# ESP32_IMUtracker_revA.net
KiCad netlist of a schematic drawn in EAGLE
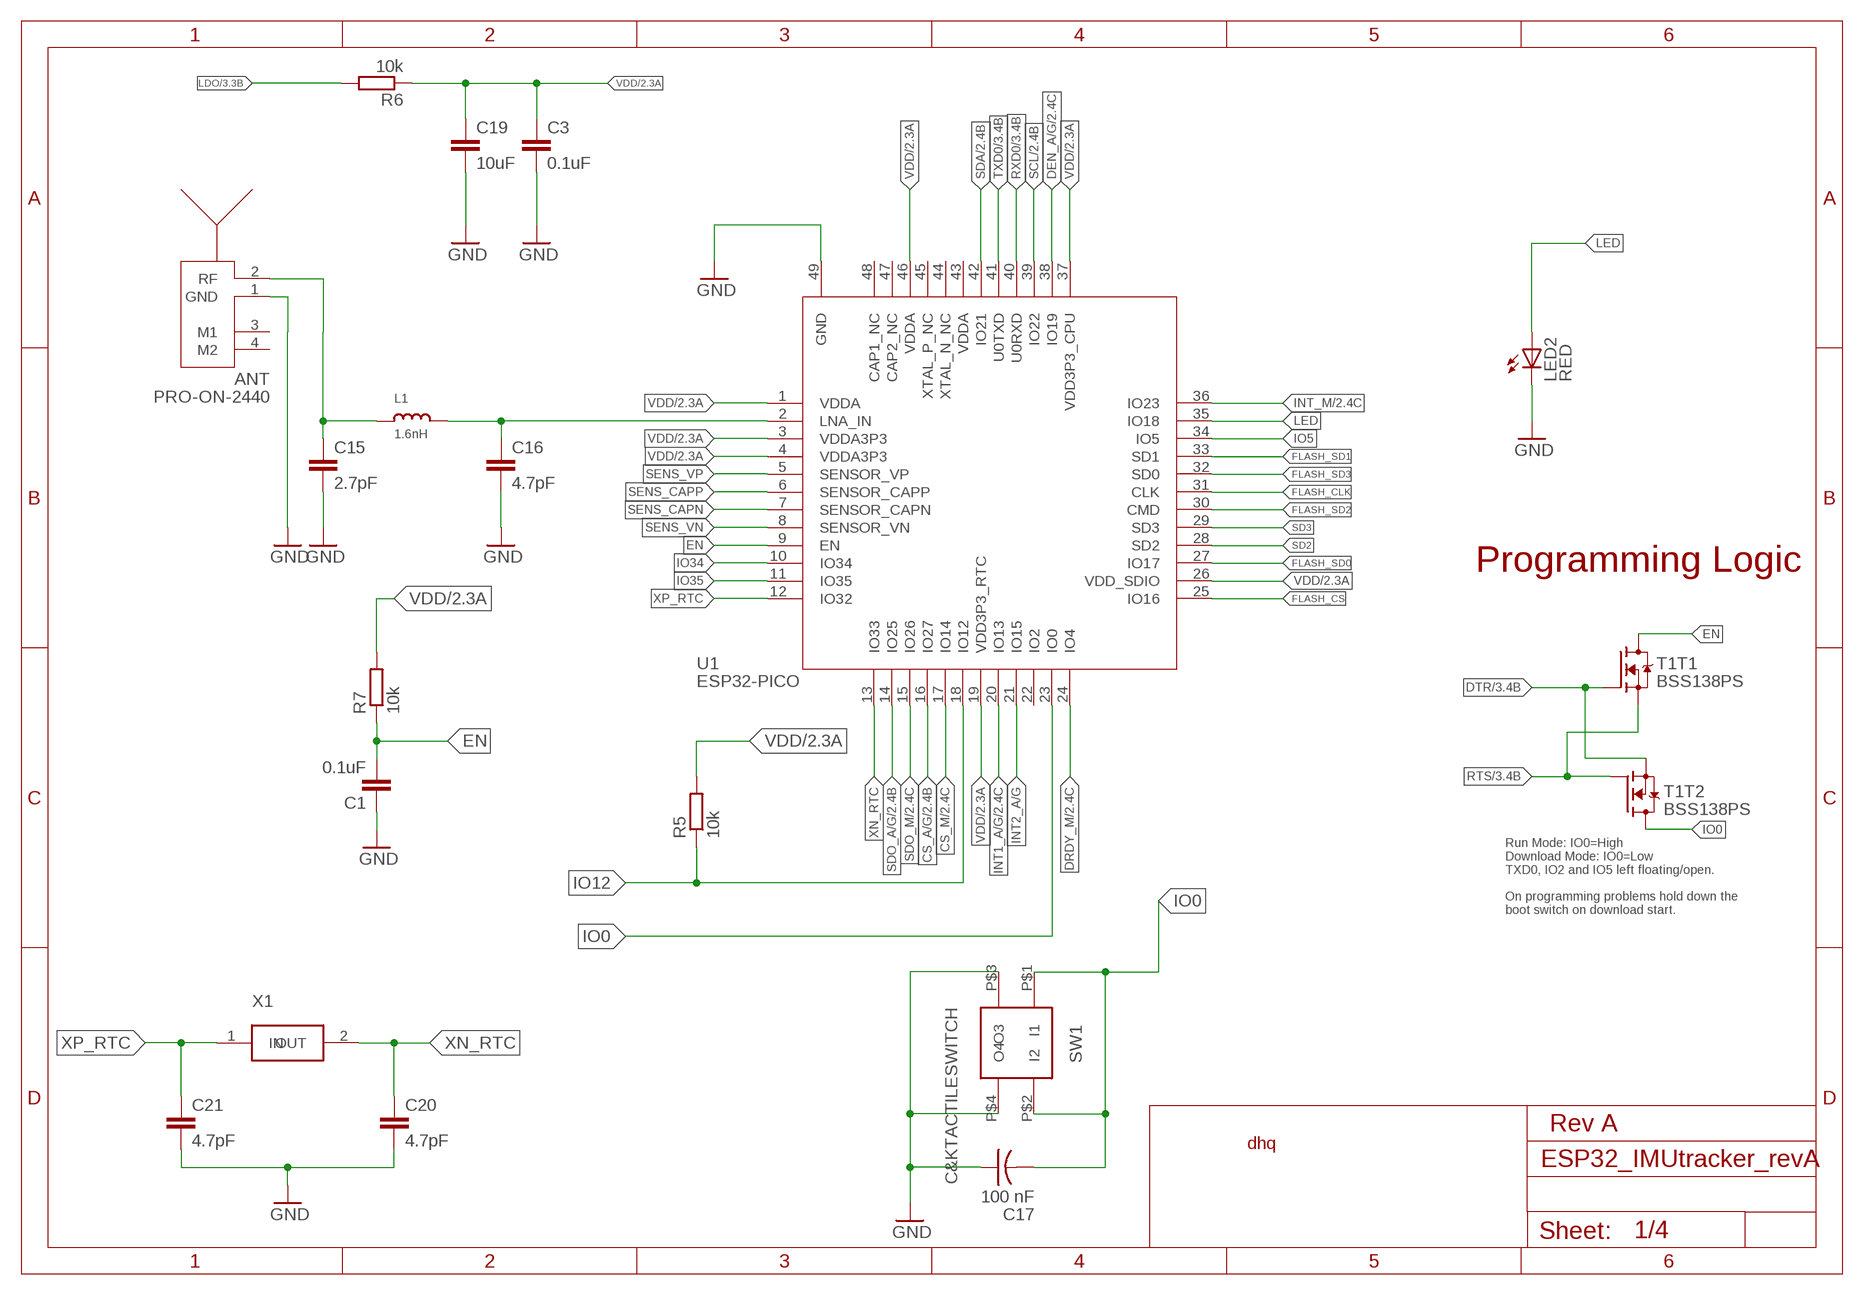
[diagram p0: schematic, sheet 1]
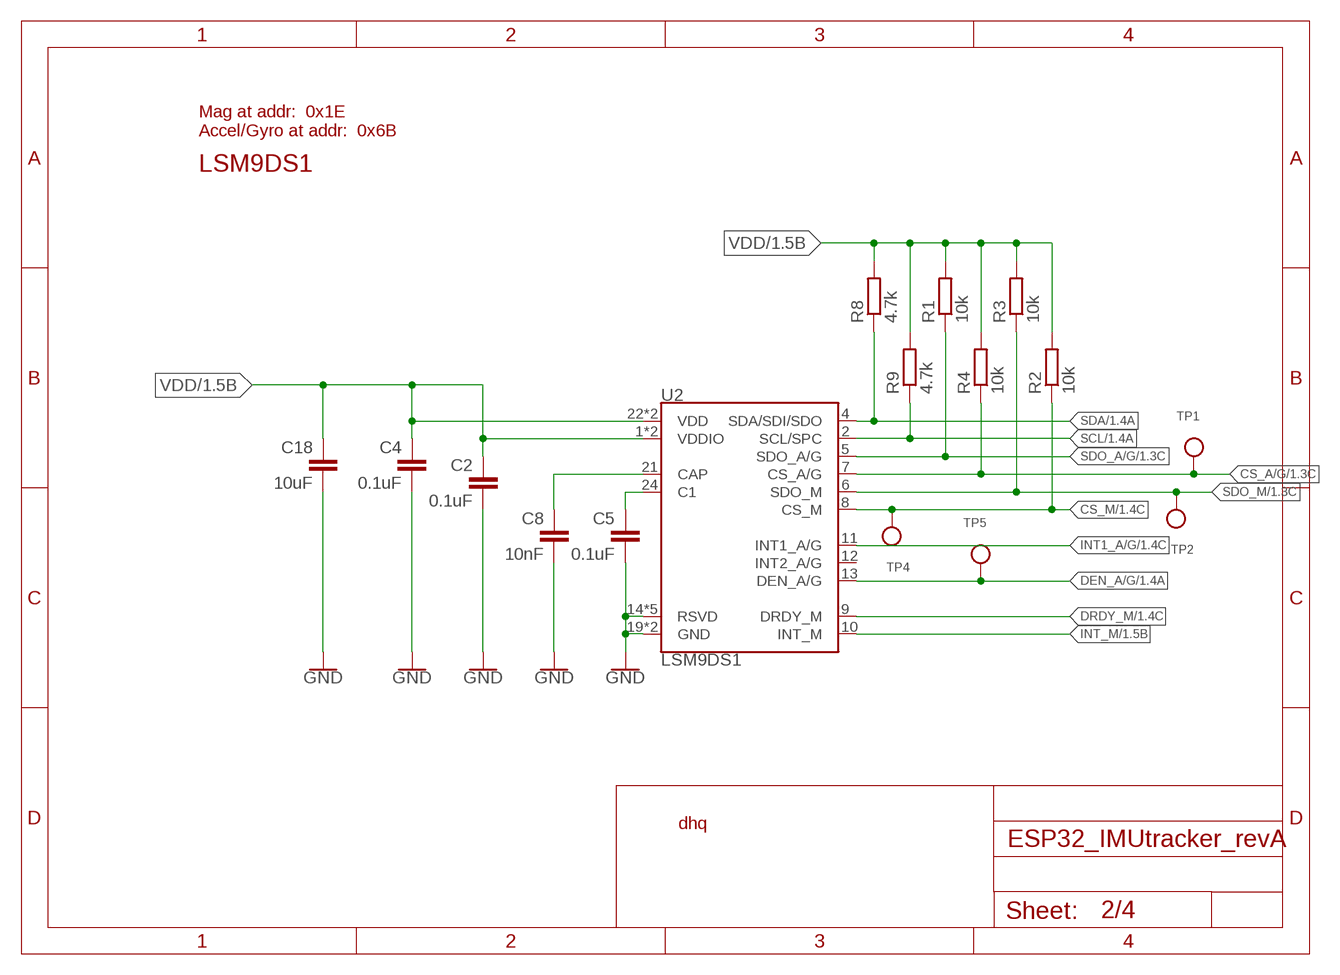
[diagram p1: schematic, sheet 2]
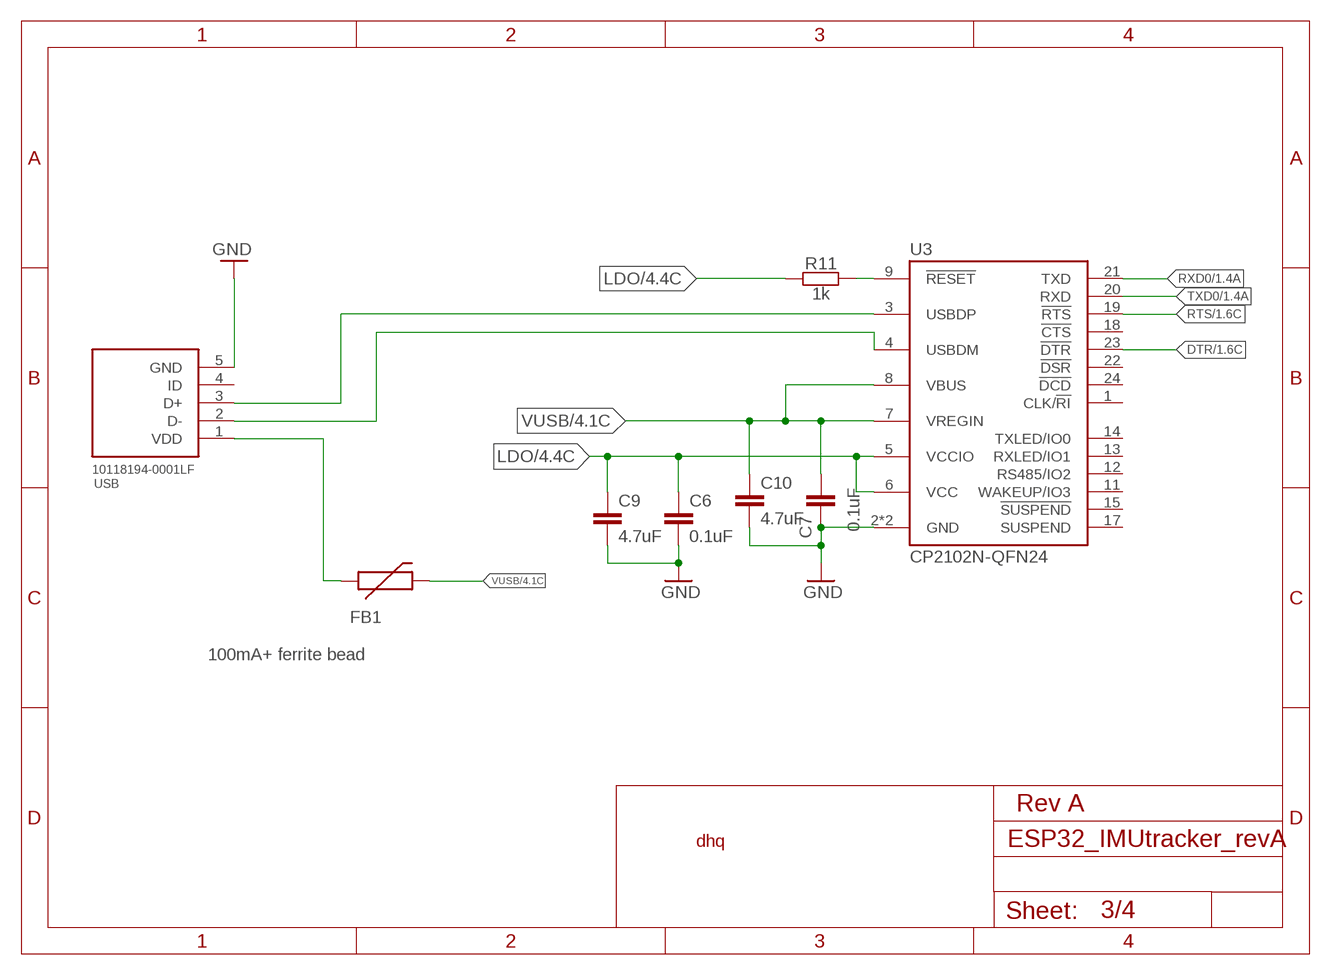
[diagram p2: schematic, sheet 3]
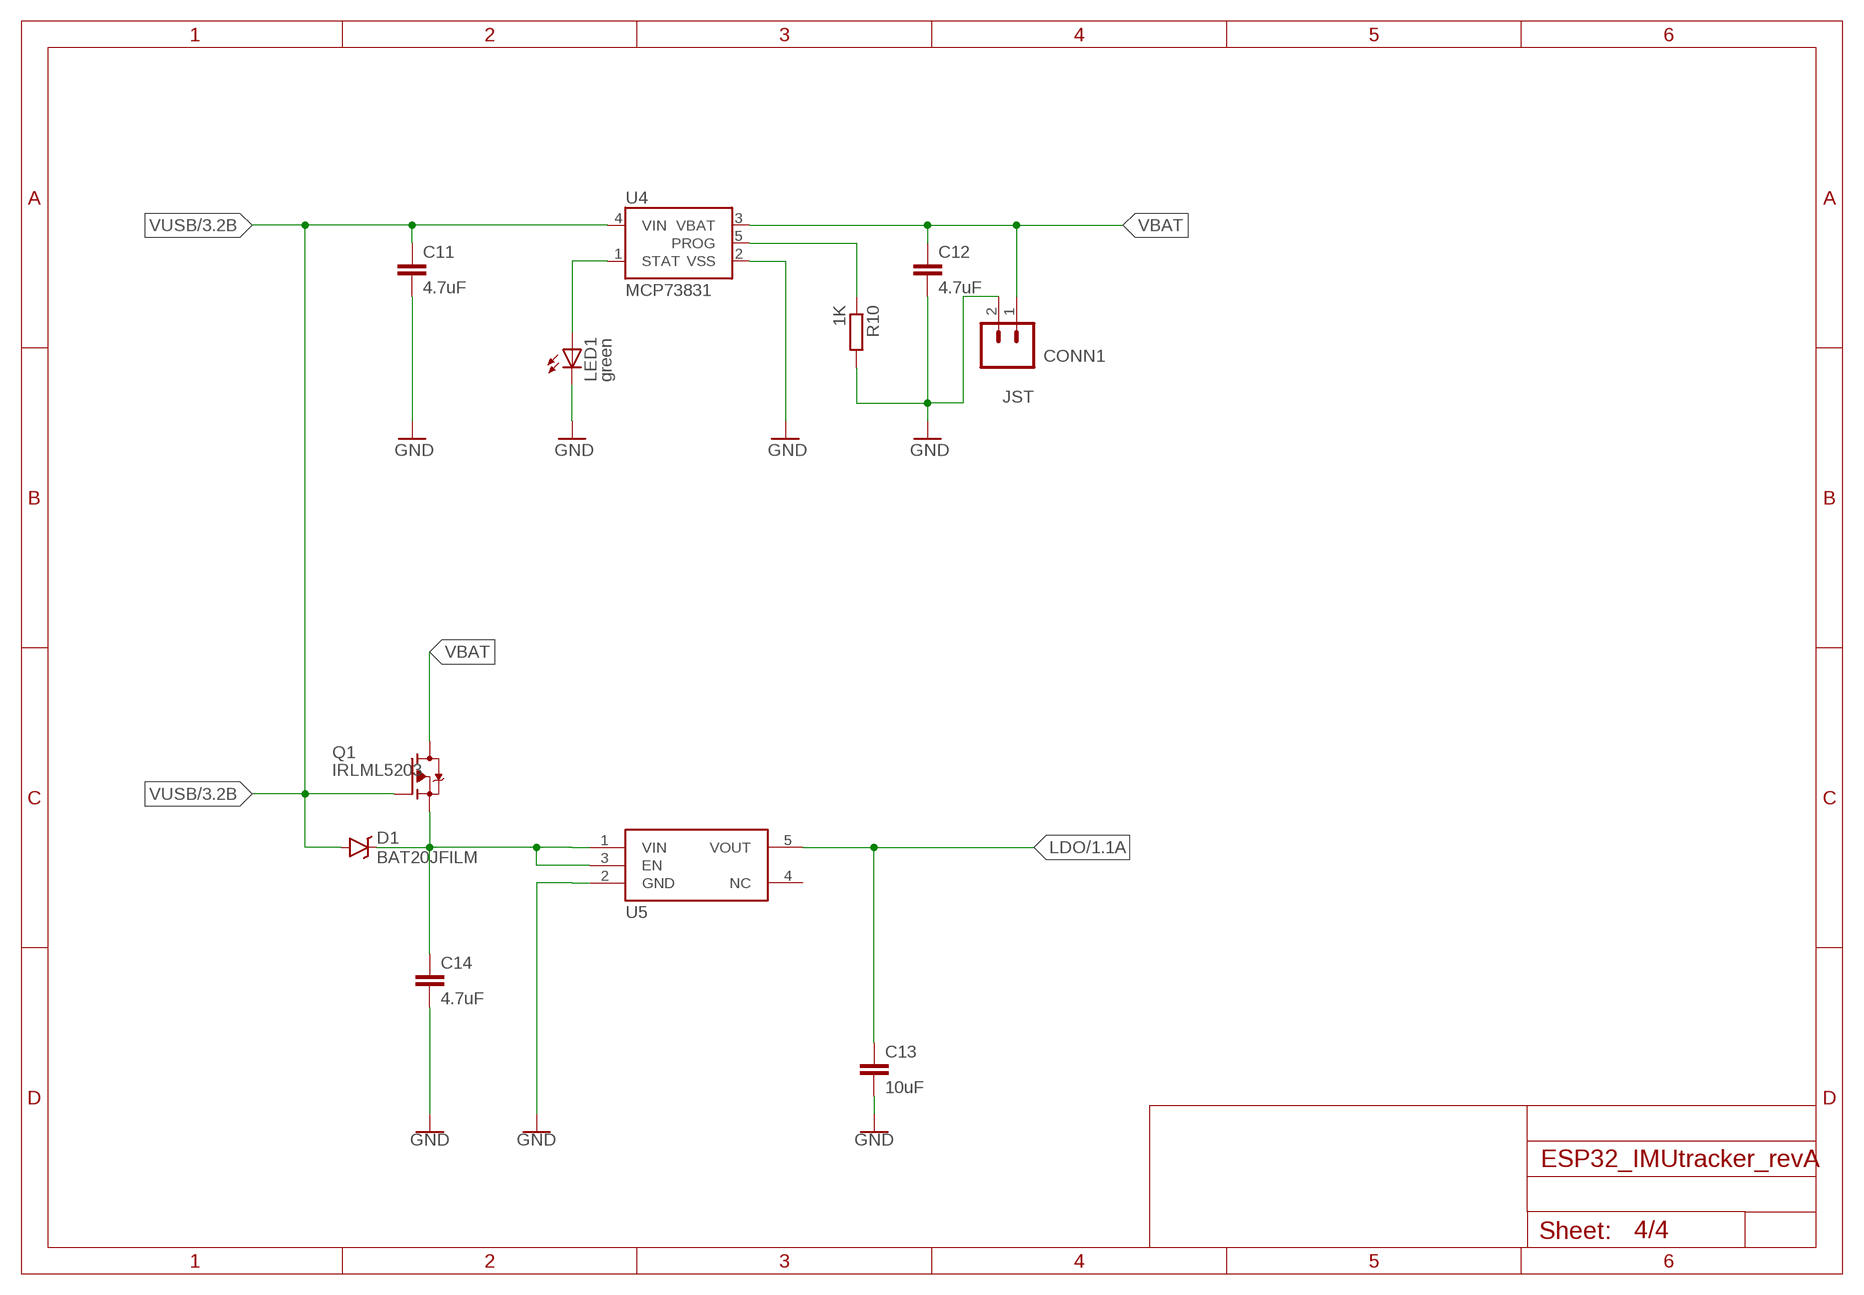
[diagram p3: schematic, sheet 4]

(export (version "E")
  (design (tool "Eeschema 10.0.6"))
  (components
    (comp (ref "C6")
      (value "0.1uF")
      (footprint "eagle-import:C0402")
      (libsource (lib "eagle-import") (part "rcl_334_C-EUC0402"))
    )
    (comp (ref "C7")
      (value "0.1uF")
      (footprint "eagle-import:C0402")
      (libsource (lib "eagle-import") (part "rcl_334_C-EUC0402"))
    )
    (comp (ref "C9")
      (value "4.7uF")
      (footprint "eagle-import:C0603")
      (libsource (lib "eagle-import") (part "rcl_334_C-EUC0603"))
    )
    (comp (ref "C10")
      (value "4.7uF")
      (footprint "eagle-import:C0603")
      (libsource (lib "eagle-import") (part "rcl_334_C-EUC0603"))
    )
    (comp (ref "FB1")
      (value "100mA+ ferrite bead")
      (footprint "eagle-import:0603")
      (libsource (lib "eagle-import") (part "PTC0603"))
    )
    (comp (ref "R11")
      (value "1k")
      (footprint "eagle-import:C0402")
      (libsource (lib "eagle-import") (part "RESISTOR-0402"))
    )
    (comp (ref "U3")
      (value "CP2102N-QFN24")
      (footprint "eagle-import:QFN24-PAD")
      (libsource (lib "eagle-import") (part "CP2102N-QFN24"))
    )
    (comp (ref "USB")
      (value "10118194-0001LF")
      (footprint "eagle-import:FRAMATOME_10118194-0001LF")
      (libsource (lib "eagle-import") (part "10118194-0001LF"))
    )
    (comp (ref "C11")
      (value "4.7uF")
      (footprint "eagle-import:C0603")
      (libsource (lib "eagle-import") (part "C-EUC0603"))
    )
    (comp (ref "C12")
      (value "4.7uF")
      (footprint "eagle-import:C0603")
      (libsource (lib "eagle-import") (part "C-EUC0603"))
    )
    (comp (ref "C13")
      (value "10uF")
      (footprint "eagle-import:C0603")
      (libsource (lib "eagle-import") (part "rcl_334_C-EUC0603"))
    )
    (comp (ref "C14")
      (value "4.7uF")
      (footprint "eagle-import:C0603")
      (libsource (lib "eagle-import") (part "rcl_334_C-EUC0603"))
    )
    (comp (ref "CONN1")
      (value "JST")
      (footprint "eagle-import:SPARKFUN-CONNECTORS_JST-2-SMD")
      (libsource (lib "eagle-import") (part "SPARKFUN-CONNECTORS_M02-JST-2MM-SMT"))
    )
    (comp (ref "D1")
      (value "BAT20JFILM")
      (footprint "eagle-import:SOD-323")
      (fields (field (name "MF") "STMicroelectronics"))
      (libsource (lib "eagle-import") (part "BAT20JFILM"))
    )
    (comp (ref "LED1")
      (value "green")
      (footprint "eagle-import:C0603")
      (libsource (lib "eagle-import") (part "LED-0603"))
    )
    (comp (ref "Q1")
      (value "IRLML5203")
      (footprint "eagle-import:SOT-23")
      (libsource (lib "eagle-import") (part "TRANSISTOR_FET_TSM2301CX"))
    )
    (comp (ref "R10")
      (value "1K")
      (footprint "eagle-import:R0402")
      (libsource (lib "eagle-import") (part "R-EU_R0402"))
    )
    (comp (ref "U4")
      (value "MCP73831")
      (footprint "eagle-import:SOT23-5")
      (libsource (lib "eagle-import") (part "MCP73831"))
    )
    (comp (ref "U5")
      (value "AP2112")
      (footprint "eagle-import:SOT95P280X145-5N")
      (libsource (lib "eagle-import") (part "AP2112"))
    )
    (comp (ref "C2")
      (value "0.1uF")
      (footprint "eagle-import:0402")
      (libsource (lib "eagle-import") (part "0.1UF-0402-16V-10%"))
    )
    (comp (ref "C4")
      (value "0.1uF")
      (footprint "eagle-import:0402")
      (libsource (lib "eagle-import") (part "0.1UF-0402-16V-10%"))
    )
    (comp (ref "C5")
      (value "0.1uF")
      (footprint "eagle-import:0402")
      (libsource (lib "eagle-import") (part "0.1UF-0402-16V-10%"))
    )
    (comp (ref "C8")
      (value "10nF")
      (footprint "eagle-import:C0402")
      (libsource (lib "eagle-import") (part "rcl_334_C-EUC0402"))
    )
    (comp (ref "C18")
      (value "10uF")
      (footprint "eagle-import:0603")
      (libsource (lib "eagle-import") (part "10UF-0603-6.3V-20%"))
    )
    (comp (ref "R1")
      (value "10k")
      (footprint "eagle-import:R0402")
      (libsource (lib "eagle-import") (part "R-EU_R0402"))
    )
    (comp (ref "R2")
      (value "10k")
      (footprint "eagle-import:R0402")
      (libsource (lib "eagle-import") (part "R-EU_R0402"))
    )
    (comp (ref "R3")
      (value "10k")
      (footprint "eagle-import:R0402")
      (libsource (lib "eagle-import") (part "R-EU_R0402"))
    )
    (comp (ref "R4")
      (value "10k")
      (footprint "eagle-import:R0402")
      (libsource (lib "eagle-import") (part "R-EU_R0402"))
    )
    (comp (ref "R8")
      (value "4.7k")
      (footprint "eagle-import:R0402")
      (libsource (lib "eagle-import") (part "R-EU_R0402"))
    )
    (comp (ref "R9")
      (value "4.7k")
      (footprint "eagle-import:R0402")
      (libsource (lib "eagle-import") (part "R-EU_R0402"))
    )
    (comp (ref "TP1")
      (value "TESTPOINTROUND0.5MM")
      (footprint "eagle-import:TESTPOINT_ROUND_0.5MM")
      (libsource (lib "eagle-import") (part "TESTPOINTROUND0.5MM"))
    )
    (comp (ref "TP2")
      (value "TESTPOINTROUND0.5MM")
      (footprint "eagle-import:TESTPOINT_ROUND_0.5MM")
      (libsource (lib "eagle-import") (part "TESTPOINTROUND0.5MM"))
    )
    (comp (ref "TP4")
      (value "TESTPOINTROUND0.5MM")
      (footprint "eagle-import:TESTPOINT_ROUND_0.5MM")
      (libsource (lib "eagle-import") (part "TESTPOINTROUND0.5MM"))
    )
    (comp (ref "TP5")
      (value "TESTPOINTROUND0.5MM")
      (footprint "eagle-import:TESTPOINT_ROUND_0.5MM")
      (libsource (lib "eagle-import") (part "TESTPOINTROUND0.5MM"))
    )
    (comp (ref "U2")
      (value "LSM9DS1")
      (footprint "eagle-import:LGA-24-3.5X3")
      (libsource (lib "eagle-import") (part "LSM9DS1"))
    )
    (comp (ref "ANT")
      (value "PRO-ON-2440")
      (footprint "eagle-import:ONBOARDSMD")
      (fields (field (name "SPICEPREFIX") "E"))
      (libsource (lib "eagle-import") (part "PRO-ON-2440"))
    )
    (comp (ref "C1")
      (value "0.1uF")
      (footprint "eagle-import:C0402")
      (libsource (lib "eagle-import") (part "rcl_334_C-EUC0402"))
    )
    (comp (ref "C3")
      (value "0.1uF")
      (footprint "eagle-import:C0402")
      (libsource (lib "eagle-import") (part "rcl_334_C-EUC0402"))
    )
    (comp (ref "C15")
      (value "2.7pF")
      (footprint "eagle-import:C0402")
      (libsource (lib "eagle-import") (part "rcl_334_C-EUC0402"))
    )
    (comp (ref "C16")
      (value "4.7pF")
      (footprint "eagle-import:C0402")
      (libsource (lib "eagle-import") (part "rcl_334_C-EUC0402"))
    )
    (comp (ref "C17")
      (value "100 nF")
      (footprint "eagle-import:C0402_B")
      (libsource (lib "eagle-import") (part "C-US"))
    )
    (comp (ref "C19")
      (value "10uF")
      (footprint "eagle-import:C0603")
      (libsource (lib "eagle-import") (part "rcl_334_C-EUC0603"))
    )
    (comp (ref "C20")
      (value "4.7pF")
      (footprint "eagle-import:C0402")
      (libsource (lib "eagle-import") (part "rcl_334_C-EUC0402"))
    )
    (comp (ref "C21")
      (value "4.7pF")
      (footprint "eagle-import:C0402")
      (libsource (lib "eagle-import") (part "rcl_334_C-EUC0402"))
    )
    (comp (ref "L1")
      (value "1.6nH")
      (footprint "eagle-import:0603")
      (libsource (lib "eagle-import") (part "INDUCTOR0603"))
    )
    (comp (ref "LED2")
      (value "RED")
      (footprint "eagle-import:CHIP-LED0603")
      (libsource (lib "eagle-import") (part "LEDCHIP-LED0603"))
    )
    (comp (ref "R5")
      (value "10k")
      (footprint "eagle-import:R0402")
      (libsource (lib "eagle-import") (part "R-EU_R0402"))
    )
    (comp (ref "R6")
      (value "10k")
      (footprint "eagle-import:R0402")
      (libsource (lib "eagle-import") (part "R-EU_R0402"))
    )
    (comp (ref "R7")
      (value "10k")
      (footprint "eagle-import:R0402")
      (libsource (lib "eagle-import") (part "R-EU_R0402"))
    )
    (comp (ref "SW1")
      (value "C&KTACTILESWITCH")
      (footprint "eagle-import:C&KTACTILESWITCH")
      (libsource (lib "eagle-import") (part "C&KTACTILESWITCH"))
    )
    (comp (ref "T1")
      (value "BSS138PS")
      (footprint "eagle-import:SOT363")
      (libsource (lib "eagle-import") (part "BSS138PS"))
    )
    (comp (ref "U1")
      (value "ESP32-PICO")
      (footprint "eagle-import:QFN48")
      (libsource (lib "eagle-import") (part "ESP32-PICO"))
    )
    (comp (ref "X1")
      (value "ST2012SB")
      (footprint "eagle-import:ST2012SB")
      (libsource (lib "eagle-import") (part "ST2012SB"))
    )
  )
  (nets
    (net (code "1") (name "CS_A{slash}G") (class "Default")
      (node (ref "R4") (pin "1") (pinfunction "1_1") (pintype "passive"))
      (node (ref "TP1") (pin "P$1") (pinfunction "P$1_P$1") (pintype "bidirectional"))
      (node (ref "U1") (pin "16") (pinfunction "IO27_16") (pintype "bidirectional"))
      (node (ref "U2") (pin "7") (pinfunction "CS_A/G_7") (pintype "bidirectional"))
    )
    (net (code "2") (name "CS_M") (class "Default")
      (node (ref "R2") (pin "1") (pinfunction "1_1") (pintype "passive"))
      (node (ref "TP4") (pin "P$1") (pinfunction "P$1_P$1") (pintype "bidirectional"))
      (node (ref "U1") (pin "17") (pinfunction "IO14_17") (pintype "bidirectional"))
      (node (ref "U2") (pin "8") (pinfunction "CS_M_8") (pintype "bidirectional"))
    )
    (net (code "3") (name "DEN_A{slash}G") (class "Default")
      (node (ref "TP5") (pin "P$1") (pinfunction "P$1_P$1") (pintype "bidirectional"))
      (node (ref "U1") (pin "38") (pinfunction "IO19_38") (pintype "bidirectional"))
      (node (ref "U2") (pin "13") (pinfunction "DEN_A/G_13") (pintype "bidirectional"))
    )
    (net (code "4") (name "DRDY_M") (class "Default")
      (node (ref "U1") (pin "24") (pinfunction "IO4_24") (pintype "bidirectional"))
      (node (ref "U2") (pin "9") (pinfunction "DRDY_M_9") (pintype "bidirectional"))
    )
    (net (code "5") (name "DTR") (class "Default")
      (node (ref "T1") (pin "2") (pinfunction "G_2") (pintype "passive"))
      (node (ref "T1") (pin "4") (pinfunction "S_4") (pintype "passive"))
      (node (ref "U3") (pin "23") (pinfunction "~{DTR}_23") (pintype "bidirectional"))
    )
    (net (code "6") (name "EN") (class "Default")
      (node (ref "C1") (pin "2") (pinfunction "2_2") (pintype "passive"))
      (node (ref "R7") (pin "1") (pinfunction "1_1") (pintype "passive"))
      (node (ref "T1") (pin "6") (pinfunction "D_6") (pintype "passive"))
      (node (ref "U1") (pin "9") (pinfunction "EN_9") (pintype "bidirectional"))
    )
    (net (code "7") (name "FLASH_CLK") (class "Default")
      (node (ref "U1") (pin "31") (pinfunction "CLK_31") (pintype "bidirectional"))
    )
    (net (code "8") (name "FLASH_CS") (class "Default")
      (node (ref "U1") (pin "25") (pinfunction "IO16_25") (pintype "bidirectional"))
    )
    (net (code "9") (name "FLASH_SD0") (class "Default")
      (node (ref "U1") (pin "27") (pinfunction "IO17_27") (pintype "bidirectional"))
    )
    (net (code "10") (name "FLASH_SD1") (class "Default")
      (node (ref "U1") (pin "33") (pinfunction "SD1_33") (pintype "bidirectional"))
    )
    (net (code "11") (name "FLASH_SD2") (class "Default")
      (node (ref "U1") (pin "30") (pinfunction "CMD_30") (pintype "bidirectional"))
    )
    (net (code "12") (name "FLASH_SD3") (class "Default")
      (node (ref "U1") (pin "32") (pinfunction "SD0_32") (pintype "bidirectional"))
    )
    (net (code "13") (name "GND") (class "Default")
      (node (ref "ANT") (pin "1") (pinfunction "GND_1") (pintype "power_in"))
      (node (ref "C1") (pin "1") (pinfunction "1_1") (pintype "passive"))
      (node (ref "C10") (pin "2") (pinfunction "2_2") (pintype "passive"))
      (node (ref "C11") (pin "2") (pinfunction "2_2") (pintype "passive"))
      (node (ref "C12") (pin "2") (pinfunction "2_2") (pintype "passive"))
      (node (ref "C13") (pin "2") (pinfunction "2_2") (pintype "passive"))
      (node (ref "C14") (pin "2") (pinfunction "2_2") (pintype "passive"))
      (node (ref "C15") (pin "2") (pinfunction "2_2") (pintype "passive"))
      (node (ref "C16") (pin "2") (pinfunction "2_2") (pintype "passive"))
      (node (ref "C17") (pin "1") (pinfunction "1_1") (pintype "passive"))
      (node (ref "C18") (pin "2") (pinfunction "2_2") (pintype "passive"))
      (node (ref "C19") (pin "2") (pinfunction "2_2") (pintype "passive"))
      (node (ref "C2") (pin "2") (pinfunction "2_2") (pintype "passive"))
      (node (ref "C20") (pin "2") (pinfunction "2_2") (pintype "passive"))
      (node (ref "C21") (pin "2") (pinfunction "2_2") (pintype "passive"))
      (node (ref "C3") (pin "2") (pinfunction "2_2") (pintype "passive"))
      (node (ref "C4") (pin "2") (pinfunction "2_2") (pintype "passive"))
      (node (ref "C5") (pin "2") (pinfunction "2_2") (pintype "passive"))
      (node (ref "C6") (pin "2") (pinfunction "2_2") (pintype "passive"))
      (node (ref "C7") (pin "1") (pinfunction "1_1") (pintype "passive"))
      (node (ref "C8") (pin "2") (pinfunction "2_2") (pintype "passive"))
      (node (ref "C9") (pin "2") (pinfunction "2_2") (pintype "passive"))
      (node (ref "CONN1") (pin "2") (pinfunction "1_2") (pintype "passive"))
      (node (ref "LED1") (pin "C") (pinfunction "C_C") (pintype "passive"))
      (node (ref "LED2") (pin "C") (pinfunction "C_C") (pintype "passive"))
      (node (ref "R10") (pin "2") (pinfunction "2_2") (pintype "passive"))
      (node (ref "SW1") (pin "P$3") (pinfunction "O3_P$3") (pintype "bidirectional"))
      (node (ref "SW1") (pin "P$4") (pinfunction "O4_P$4") (pintype "bidirectional"))
      (node (ref "U1") (pin "49") (pinfunction "GND_49") (pintype "bidirectional"))
      (node (ref "U2") (pin "14") (pinfunction "RSVD_14") (pintype "bidirectional"))
      (node (ref "U2") (pin "15") (pinfunction "RSVD_15") (pintype "bidirectional"))
      (node (ref "U2") (pin "16") (pinfunction "RSVD_16") (pintype "bidirectional"))
      (node (ref "U2") (pin "17") (pinfunction "RSVD_17") (pintype "bidirectional"))
      (node (ref "U2") (pin "18") (pinfunction "RSVD_18") (pintype "bidirectional"))
      (node (ref "U2") (pin "19") (pinfunction "GND_19") (pintype "bidirectional"))
      (node (ref "U2") (pin "20") (pinfunction "GND_20") (pintype "bidirectional"))
      (node (ref "U3") (pin "2") (pinfunction "GND_2") (pintype "power_in"))
      (node (ref "U3") (pin "TP") (pinfunction "GND_TP") (pintype "power_in"))
      (node (ref "U4") (pin "2") (pinfunction "VSS_2") (pintype "power_in"))
      (node (ref "U5") (pin "2") (pinfunction "GND_2") (pintype "power_in"))
      (node (ref "USB") (pin "5") (pinfunction "GND_5") (pintype "power_in"))
    )
    (net (code "14") (name "INT1_A{slash}G") (class "Default")
      (node (ref "U1") (pin "20") (pinfunction "IO13_20") (pintype "bidirectional"))
      (node (ref "U2") (pin "11") (pinfunction "INT1_A/G_11") (pintype "bidirectional"))
    )
    (net (code "15") (name "INT2_A{slash}G") (class "Default")
      (node (ref "U1") (pin "21") (pinfunction "IO15_21") (pintype "bidirectional"))
    )
    (net (code "16") (name "INT_M") (class "Default")
      (node (ref "U1") (pin "36") (pinfunction "IO23_36") (pintype "bidirectional"))
      (node (ref "U2") (pin "10") (pinfunction "INT_M_10") (pintype "bidirectional"))
    )
    (net (code "17") (name "IO0") (class "Default")
      (node (ref "C17") (pin "2") (pinfunction "2_2") (pintype "passive"))
      (node (ref "SW1") (pin "P$1") (pinfunction "I1_P$1") (pintype "bidirectional"))
      (node (ref "SW1") (pin "P$2") (pinfunction "I2_P$2") (pintype "bidirectional"))
      (node (ref "T1") (pin "3") (pinfunction "D_3") (pintype "passive"))
      (node (ref "U1") (pin "23") (pinfunction "IO0_23") (pintype "bidirectional"))
    )
    (net (code "18") (name "IO5") (class "Default")
      (node (ref "U1") (pin "34") (pinfunction "IO5_34") (pintype "bidirectional"))
    )
    (net (code "19") (name "IO12") (class "Default")
      (node (ref "R5") (pin "1") (pinfunction "1_1") (pintype "passive"))
      (node (ref "U1") (pin "18") (pinfunction "IO12_18") (pintype "bidirectional"))
    )
    (net (code "20") (name "IO34") (class "Default")
      (node (ref "U1") (pin "10") (pinfunction "IO34_10") (pintype "bidirectional"))
    )
    (net (code "21") (name "IO35") (class "Default")
      (node (ref "U1") (pin "11") (pinfunction "IO35_11") (pintype "bidirectional"))
    )
    (net (code "22") (name "LDO") (class "Default")
      (node (ref "C13") (pin "1") (pinfunction "1_1") (pintype "passive"))
      (node (ref "C6") (pin "1") (pinfunction "1_1") (pintype "passive"))
      (node (ref "C9") (pin "1") (pinfunction "1_1") (pintype "passive"))
      (node (ref "R11") (pin "1") (pinfunction "1_1") (pintype "passive"))
      (node (ref "R6") (pin "2") (pinfunction "2_2") (pintype "passive"))
      (node (ref "U3") (pin "5") (pinfunction "VCCIO_5") (pintype "power_in"))
      (node (ref "U3") (pin "6") (pinfunction "VCC_6") (pintype "power_in"))
      (node (ref "U5") (pin "5") (pinfunction "VOUT_5") (pintype "bidirectional"))
    )
    (net (code "23") (name "LED") (class "Default")
      (node (ref "LED2") (pin "A") (pinfunction "A_A") (pintype "passive"))
      (node (ref "U1") (pin "35") (pinfunction "IO18_35") (pintype "bidirectional"))
    )
    (net (code "24") (name "Net-(ANT-RF)") (class "Default")
      (node (ref "ANT") (pin "2") (pinfunction "RF_2") (pintype "bidirectional"))
      (node (ref "C15") (pin "1") (pinfunction "1_1") (pintype "passive"))
      (node (ref "L1") (pin "1") (pinfunction "1_1") (pintype "passive"))
    )
    (net (code "25") (name "Net-(Q1-S)") (class "Default")
      (node (ref "C14") (pin "1") (pinfunction "1_1") (pintype "passive"))
      (node (ref "D1") (pin "C") (pinfunction "C_C") (pintype "passive"))
      (node (ref "Q1") (pin "2") (pinfunction "S_2") (pintype "passive"))
      (node (ref "U5") (pin "1") (pinfunction "VIN_1") (pintype "power_in"))
      (node (ref "U5") (pin "3") (pinfunction "EN_3") (pintype "bidirectional"))
    )
    (net (code "26") (name "Net-(U1-LNA_IN)") (class "Default")
      (node (ref "C16") (pin "1") (pinfunction "1_1") (pintype "passive"))
      (node (ref "L1") (pin "2") (pinfunction "2_2") (pintype "passive"))
      (node (ref "U1") (pin "2") (pinfunction "LNA_IN_2") (pintype "bidirectional"))
    )
    (net (code "27") (name "Net-(U2-C1)") (class "Default")
      (node (ref "C5") (pin "1") (pinfunction "1_1") (pintype "passive"))
      (node (ref "U2") (pin "24") (pinfunction "C1_24") (pintype "bidirectional"))
    )
    (net (code "28") (name "Net-(U2-CAP)") (class "Default")
      (node (ref "C8") (pin "1") (pinfunction "1_1") (pintype "passive"))
      (node (ref "U2") (pin "21") (pinfunction "CAP_21") (pintype "bidirectional"))
    )
    (net (code "29") (name "Net-(U3-USBDM)") (class "Default")
      (node (ref "U3") (pin "4") (pinfunction "USBDM_4") (pintype "bidirectional"))
      (node (ref "USB") (pin "2") (pinfunction "D-_2") (pintype "bidirectional"))
    )
    (net (code "30") (name "Net-(U3-USBDP)") (class "Default")
      (node (ref "U3") (pin "3") (pinfunction "USBDP_3") (pintype "bidirectional"))
      (node (ref "USB") (pin "3") (pinfunction "D+_3") (pintype "bidirectional"))
    )
    (net (code "31") (name "Net-(U3-~{RESET})") (class "Default")
      (node (ref "R11") (pin "2") (pinfunction "2_2") (pintype "passive"))
      (node (ref "U3") (pin "9") (pinfunction "~{RESET}_9") (pintype "bidirectional"))
    )
    (net (code "32") (name "Net-(U4-PROG)") (class "Default")
      (node (ref "R10") (pin "1") (pinfunction "1_1") (pintype "passive"))
      (node (ref "U4") (pin "5") (pinfunction "PROG_5") (pintype "input"))
    )
    (net (code "33") (name "Net-(U4-STAT)") (class "Default")
      (node (ref "LED1") (pin "A") (pinfunction "A_A") (pintype "passive"))
      (node (ref "U4") (pin "1") (pinfunction "STAT_1") (pintype "output"))
    )
    (net (code "34") (name "Net-(USB-VDD)") (class "Default")
      (node (ref "FB1") (pin "1") (pinfunction "1_1") (pintype "bidirectional"))
      (node (ref "USB") (pin "1") (pinfunction "VDD_1") (pintype "power_in"))
    )
    (net (code "35") (name "RTS") (class "Default")
      (node (ref "T1") (pin "1") (pinfunction "S_1") (pintype "passive"))
      (node (ref "T1") (pin "5") (pinfunction "G_5") (pintype "passive"))
      (node (ref "U3") (pin "19") (pinfunction "~{RTS}_19") (pintype "bidirectional"))
    )
    (net (code "36") (name "RXD0") (class "Default")
      (node (ref "U1") (pin "40") (pinfunction "U0RXD_40") (pintype "bidirectional"))
      (node (ref "U3") (pin "21") (pinfunction "TXD_21") (pintype "bidirectional"))
    )
    (net (code "37") (name "SCL") (class "Default")
      (node (ref "R9") (pin "1") (pinfunction "1_1") (pintype "passive"))
      (node (ref "U1") (pin "39") (pinfunction "IO22_39") (pintype "bidirectional"))
      (node (ref "U2") (pin "2") (pinfunction "SCL/SPC_2") (pintype "bidirectional"))
    )
    (net (code "38") (name "SD2") (class "Default")
      (node (ref "U1") (pin "28") (pinfunction "SD2_28") (pintype "bidirectional"))
    )
    (net (code "39") (name "SD3") (class "Default")
      (node (ref "U1") (pin "29") (pinfunction "SD3_29") (pintype "bidirectional"))
    )
    (net (code "40") (name "SDA") (class "Default")
      (node (ref "R8") (pin "1") (pinfunction "1_1") (pintype "passive"))
      (node (ref "U1") (pin "42") (pinfunction "IO21_42") (pintype "bidirectional"))
      (node (ref "U2") (pin "4") (pinfunction "SDA/SDI/SDO_4") (pintype "bidirectional"))
    )
    (net (code "41") (name "SDO_A{slash}G") (class "Default")
      (node (ref "R1") (pin "1") (pinfunction "1_1") (pintype "passive"))
      (node (ref "U1") (pin "14") (pinfunction "IO25_14") (pintype "bidirectional"))
      (node (ref "U2") (pin "5") (pinfunction "SDO_A/G_5") (pintype "bidirectional"))
    )
    (net (code "42") (name "SDO_M") (class "Default")
      (node (ref "R3") (pin "1") (pinfunction "1_1") (pintype "passive"))
      (node (ref "TP2") (pin "P$1") (pinfunction "P$1_P$1") (pintype "bidirectional"))
      (node (ref "U1") (pin "15") (pinfunction "IO26_15") (pintype "bidirectional"))
      (node (ref "U2") (pin "6") (pinfunction "SDO_M_6") (pintype "bidirectional"))
    )
    (net (code "43") (name "SENS_CAPN") (class "Default")
      (node (ref "U1") (pin "7") (pinfunction "SENSOR_CAPN_7") (pintype "bidirectional"))
    )
    (net (code "44") (name "SENS_CAPP") (class "Default")
      (node (ref "U1") (pin "6") (pinfunction "SENSOR_CAPP_6") (pintype "bidirectional"))
    )
    (net (code "45") (name "SENS_VN") (class "Default")
      (node (ref "U1") (pin "8") (pinfunction "SENSOR_VN_8") (pintype "bidirectional"))
    )
    (net (code "46") (name "SENS_VP") (class "Default")
      (node (ref "U1") (pin "5") (pinfunction "SENSOR_VP_5") (pintype "bidirectional"))
    )
    (net (code "47") (name "TXD0") (class "Default")
      (node (ref "U1") (pin "41") (pinfunction "U0TXD_41") (pintype "bidirectional"))
      (node (ref "U3") (pin "20") (pinfunction "RXD_20") (pintype "bidirectional"))
    )
    (net (code "48") (name "VBAT") (class "Default")
      (node (ref "C12") (pin "1") (pinfunction "1_1") (pintype "passive"))
      (node (ref "CONN1") (pin "1") (pinfunction "2_1") (pintype "passive"))
      (node (ref "Q1") (pin "3") (pinfunction "D_3") (pintype "passive"))
      (node (ref "U4") (pin "3") (pinfunction "VBAT_3") (pintype "power_in"))
    )
    (net (code "49") (name "VDD") (class "Default")
      (node (ref "C18") (pin "1") (pinfunction "1_1") (pintype "passive"))
      (node (ref "C19") (pin "1") (pinfunction "1_1") (pintype "passive"))
      (node (ref "C2") (pin "1") (pinfunction "1_1") (pintype "passive"))
      (node (ref "C3") (pin "1") (pinfunction "1_1") (pintype "passive"))
      (node (ref "C4") (pin "1") (pinfunction "1_1") (pintype "passive"))
      (node (ref "R1") (pin "2") (pinfunction "2_2") (pintype "passive"))
      (node (ref "R2") (pin "2") (pinfunction "2_2") (pintype "passive"))
      (node (ref "R3") (pin "2") (pinfunction "2_2") (pintype "passive"))
      (node (ref "R4") (pin "2") (pinfunction "2_2") (pintype "passive"))
      (node (ref "R5") (pin "2") (pinfunction "2_2") (pintype "passive"))
      (node (ref "R6") (pin "1") (pinfunction "1_1") (pintype "passive"))
      (node (ref "R7") (pin "2") (pinfunction "2_2") (pintype "passive"))
      (node (ref "R8") (pin "2") (pinfunction "2_2") (pintype "passive"))
      (node (ref "R9") (pin "2") (pinfunction "2_2") (pintype "passive"))
      (node (ref "U1") (pin "1") (pinfunction "VDDA_1") (pintype "bidirectional"))
      (node (ref "U1") (pin "19") (pinfunction "VDD3P3_RTC_19") (pintype "bidirectional"))
      (node (ref "U1") (pin "26") (pinfunction "VDD_SDIO_26") (pintype "bidirectional"))
      (node (ref "U1") (pin "3") (pinfunction "VDDA3P3_3") (pintype "bidirectional"))
      (node (ref "U1") (pin "37") (pinfunction "VDD3P3_CPU_37") (pintype "bidirectional"))
      (node (ref "U1") (pin "4") (pinfunction "VDDA3P3_4") (pintype "bidirectional"))
      (node (ref "U1") (pin "46") (pinfunction "VDDA_46") (pintype "bidirectional"))
      (node (ref "U2") (pin "1") (pinfunction "VDDIO_1") (pintype "bidirectional"))
      (node (ref "U2") (pin "22") (pinfunction "VDD_22") (pintype "bidirectional"))
      (node (ref "U2") (pin "23") (pinfunction "VDD_23") (pintype "bidirectional"))
      (node (ref "U2") (pin "3") (pinfunction "VDDIO_3") (pintype "bidirectional"))
    )
    (net (code "50") (name "VUSB") (class "Default")
      (node (ref "C10") (pin "1") (pinfunction "1_1") (pintype "passive"))
      (node (ref "C11") (pin "1") (pinfunction "1_1") (pintype "passive"))
      (node (ref "C7") (pin "2") (pinfunction "2_2") (pintype "passive"))
      (node (ref "D1") (pin "A") (pinfunction "A_A") (pintype "passive"))
      (node (ref "FB1") (pin "2") (pinfunction "2_2") (pintype "bidirectional"))
      (node (ref "Q1") (pin "1") (pinfunction "G_1") (pintype "passive"))
      (node (ref "U3") (pin "7") (pinfunction "VREGIN_7") (pintype "power_in"))
      (node (ref "U3") (pin "8") (pinfunction "VBUS_8") (pintype "power_in"))
      (node (ref "U4") (pin "4") (pinfunction "VIN_4") (pintype "power_in"))
    )
    (net (code "51") (name "XN_RTC") (class "Default")
      (node (ref "C20") (pin "1") (pinfunction "1_1") (pintype "passive"))
      (node (ref "U1") (pin "13") (pinfunction "IO33_13") (pintype "bidirectional"))
      (node (ref "X1") (pin "2") (pinfunction "OUT_2") (pintype "bidirectional"))
    )
    (net (code "52") (name "XP_RTC") (class "Default")
      (node (ref "C21") (pin "1") (pinfunction "1_1") (pintype "passive"))
      (node (ref "U1") (pin "12") (pinfunction "IO32_12") (pintype "bidirectional"))
      (node (ref "X1") (pin "1") (pinfunction "IN_1") (pintype "bidirectional"))
    )
    (net (code "53") (name "unconnected-(ANT-M1-Pad3)") (class "Default")
      (node (ref "ANT") (pin "3") (pinfunction "M1_3") (pintype "no_connect"))
    )
    (net (code "54") (name "unconnected-(ANT-M2-Pad4)") (class "Default")
      (node (ref "ANT") (pin "4") (pinfunction "M2_4") (pintype "no_connect"))
    )
    (net (code "55") (name "unconnected-(U1-CAP1_NC-Pad48)") (class "Default")
      (node (ref "U1") (pin "48") (pinfunction "CAP1_NC_48") (pintype "bidirectional"))
    )
    (net (code "56") (name "unconnected-(U1-CAP2_NC-Pad47)") (class "Default")
      (node (ref "U1") (pin "47") (pinfunction "CAP2_NC_47") (pintype "bidirectional"))
    )
    (net (code "57") (name "unconnected-(U1-IO2-Pad22)") (class "Default")
      (node (ref "U1") (pin "22") (pinfunction "IO2_22") (pintype "bidirectional"))
    )
    (net (code "58") (name "unconnected-(U1-VDDA-Pad43)") (class "Default")
      (node (ref "U1") (pin "43") (pinfunction "VDDA_43") (pintype "bidirectional"))
    )
    (net (code "59") (name "unconnected-(U1-XTAL_N_NC-Pad44)") (class "Default")
      (node (ref "U1") (pin "44") (pinfunction "XTAL_N_NC_44") (pintype "bidirectional"))
    )
    (net (code "60") (name "unconnected-(U1-XTAL_P_NC-Pad45)") (class "Default")
      (node (ref "U1") (pin "45") (pinfunction "XTAL_P_NC_45") (pintype "bidirectional"))
    )
    (net (code "61") (name "unconnected-(U2-INT2_A{slash}G-Pad12)") (class "Default")
      (node (ref "U2") (pin "12") (pinfunction "INT2_A/G_12") (pintype "bidirectional"))
    )
    (net (code "62") (name "unconnected-(U3-CLK{slash}~{RI}-Pad1)") (class "Default")
      (node (ref "U3") (pin "1") (pinfunction "CLK/~{RI}_1") (pintype "bidirectional"))
    )
    (net (code "63") (name "unconnected-(U3-RS485{slash}IO2-Pad12)") (class "Default")
      (node (ref "U3") (pin "12") (pinfunction "RS485/IO2_12") (pintype "bidirectional"))
    )
    (net (code "64") (name "unconnected-(U3-RXLED{slash}IO1-Pad13)") (class "Default")
      (node (ref "U3") (pin "13") (pinfunction "RXLED/IO1_13") (pintype "bidirectional"))
    )
    (net (code "65") (name "unconnected-(U3-SUSPEND-Pad17)") (class "Default")
      (node (ref "U3") (pin "17") (pinfunction "SUSPEND_17") (pintype "bidirectional"))
    )
    (net (code "66") (name "unconnected-(U3-TXLED{slash}IO0-Pad14)") (class "Default")
      (node (ref "U3") (pin "14") (pinfunction "TXLED/IO0_14") (pintype "bidirectional"))
    )
    (net (code "67") (name "unconnected-(U3-WAKEUP{slash}IO3-Pad11)") (class "Default")
      (node (ref "U3") (pin "11") (pinfunction "WAKEUP/IO3_11") (pintype "bidirectional"))
    )
    (net (code "68") (name "unconnected-(U3-~{CTS}-Pad18)") (class "Default")
      (node (ref "U3") (pin "18") (pinfunction "~{CTS}_18") (pintype "bidirectional"))
    )
    (net (code "69") (name "unconnected-(U3-~{DCD}-Pad24)") (class "Default")
      (node (ref "U3") (pin "24") (pinfunction "~{DCD}_24") (pintype "bidirectional"))
    )
    (net (code "70") (name "unconnected-(U3-~{DSR}-Pad22)") (class "Default")
      (node (ref "U3") (pin "22") (pinfunction "~{DSR}_22") (pintype "bidirectional"))
    )
    (net (code "71") (name "unconnected-(U3-~{SUSPEND}-Pad15)") (class "Default")
      (node (ref "U3") (pin "15") (pinfunction "~{SUSPEND}_15") (pintype "bidirectional"))
    )
    (net (code "72") (name "unconnected-(U5-NC-Pad4)") (class "Default")
      (node (ref "U5") (pin "4") (pinfunction "NC_4") (pintype "bidirectional"))
    )
    (net (code "73") (name "unconnected-(USB-ID-Pad4)") (class "Default")
      (node (ref "USB") (pin "4") (pinfunction "ID_4") (pintype "passive"))
    )
  )
)
